# EXP03_02_2104_20212241212.net
KiCad netlist of a schematic drawn in Altium Designer
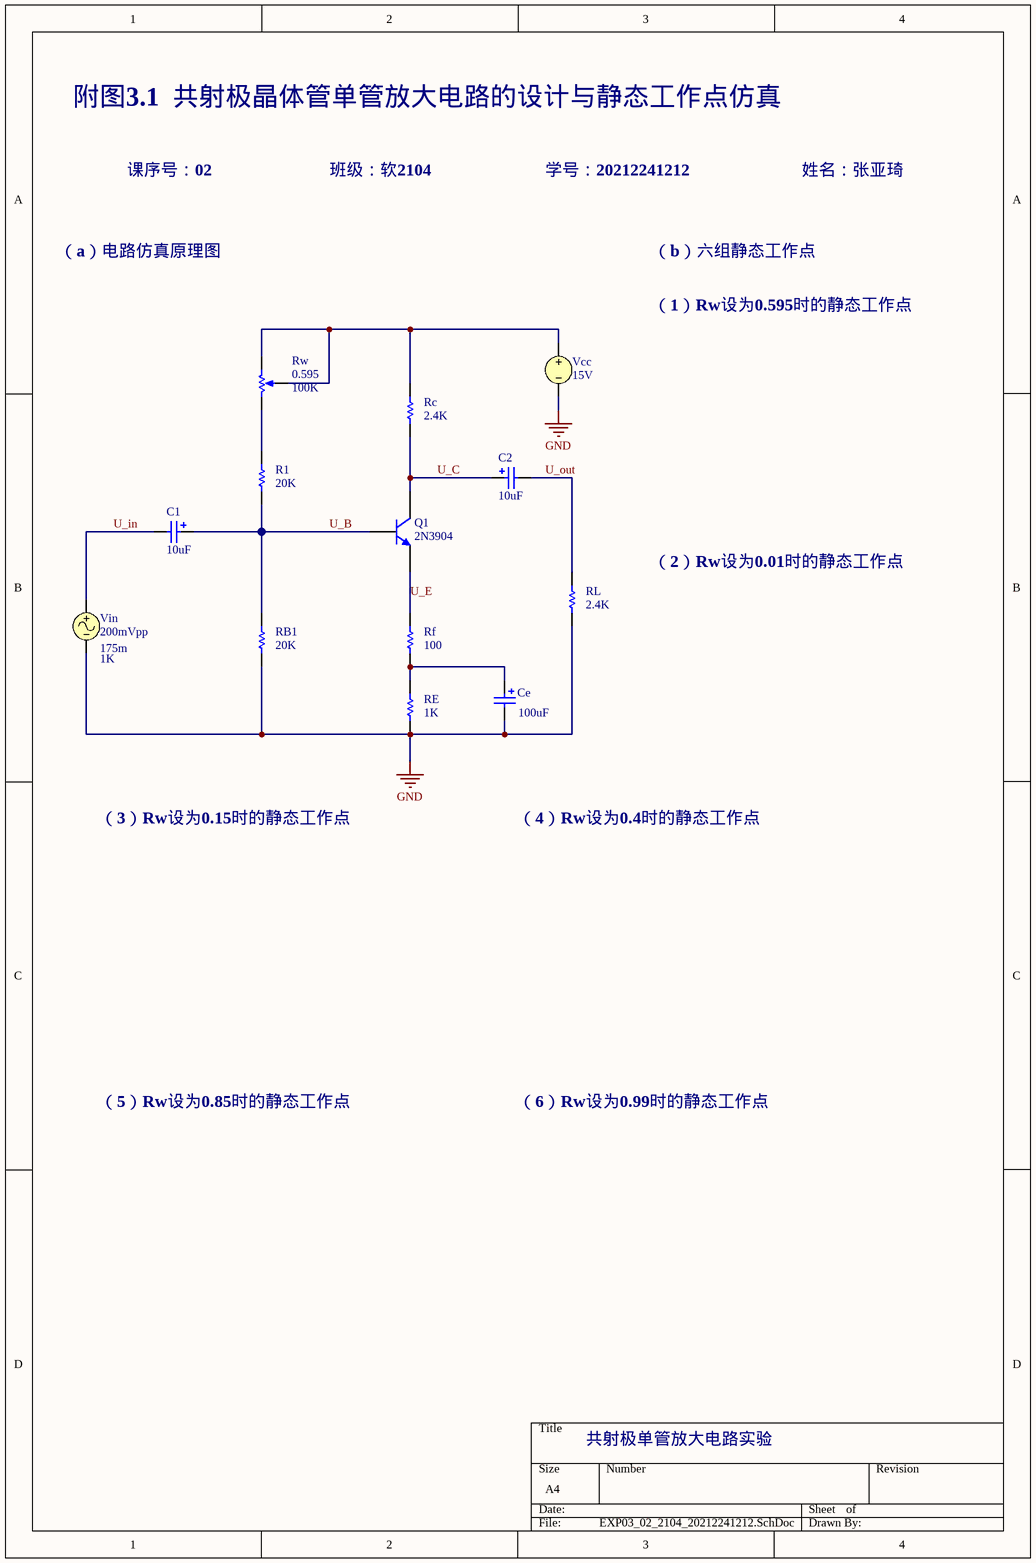
[diagram p0: EXP03_02_2104_20212241212.SchDoc]

(export (version "E")
  (design (tool "Eeschema 10.0.6"))
  (components
    (comp (ref "C1")
      (value "10uF")
      (footprint "POLAR0.8")
      (description "Polarized Capacitor (Axial)")
      (fields (field (name "PUBLISHER") "Altium Limited"))
      (libsource (lib "Miscellaneous Devices") (part "Cap Pol2"))
    )
    (comp (ref "C2")
      (value "10uF")
      (footprint "POLAR0.8")
      (description "Polarized Capacitor (Axial)")
      (fields (field (name "PUBLISHER") "Altium Limited"))
      (libsource (lib "Miscellaneous Devices") (part "Cap Pol2"))
    )
    (comp (ref "Ce")
      (value "100uF")
      (footprint "POLAR0.8")
      (description "Polarized Capacitor (Axial)")
      (fields (field (name "Comment") "Cap Pol2") (field (name "PUBLISHER") "Altium Limited"))
      (libsource (lib "") (part "Cap Pol2_1"))
    )
    (comp (ref "Q1")
      (value "2N3904")
      (footprint "TO-92A")
      (description "NPN General Purpose Amplifier")
      (fields (field (name "PUBLISHER") "Altium Limited"))
      (libsource (lib "Miscellaneous Devices") (part "2N3904"))
    )
    (comp (ref "R1")
      (value "20K")
      (footprint "AXIAL-0.3")
      (description "Resistor")
      (fields (field (name "Comment") "Res1") (field (name "PUBLISHER") "Altium Limited"))
      (libsource (lib "Miscellaneous Devices") (part "Res1"))
    )
    (comp (ref "RB1")
      (value "20K")
      (footprint "AXIAL-0.3")
      (description "Resistor")
      (fields (field (name "Comment") "Res1") (field (name "PUBLISHER") "Altium Limited"))
      (libsource (lib "Miscellaneous Devices") (part "Res1"))
    )
    (comp (ref "Rc")
      (value "2.4K")
      (footprint "AXIAL-0.3")
      (description "Resistor")
      (fields (field (name "Comment") "Res1") (field (name "PUBLISHER") "Altium Limited"))
      (libsource (lib "Miscellaneous Devices") (part "Res1"))
    )
    (comp (ref "RE")
      (value "1K")
      (footprint "AXIAL-0.3")
      (description "Resistor")
      (fields (field (name "Comment") "Res1") (field (name "PUBLISHER") "Altium Limited"))
      (libsource (lib "Miscellaneous Devices") (part "Res1"))
    )
    (comp (ref "Rf")
      (value "100")
      (footprint "AXIAL-0.3")
      (description "Resistor")
      (fields (field (name "Comment") "Res1") (field (name "PUBLISHER") "Altium Limited"))
      (libsource (lib "Miscellaneous Devices") (part "Res1"))
    )
    (comp (ref "RL")
      (value "2.4K")
      (footprint "AXIAL-0.3")
      (description "Resistor")
      (fields (field (name "Comment") "Res1") (field (name "PUBLISHER") "Altium Limited"))
      (libsource (lib "Miscellaneous Devices") (part "Res1"))
    )
    (comp (ref "Rw")
      (value "100K")
      (footprint "VR5")
      (description "Potentiometer")
      (fields
        (field (name "SET POSITION") "0.595")
        (field (name "Comment") "RPot")
        (field (name "PUBLISHER") "Altium Limited")
      )
      (libsource (lib "Miscellaneous Devices") (part "RPot"))
    )
    (comp (ref "Vcc")
      (value "15V")
      (description "Voltage Source")
      (fields (field (name "PUBLISHER") "Altium Limited"))
      (libsource (lib "Simulation Sources") (part "VSRC"))
    )
    (comp (ref "Vin")
      (value "200mVpp")
      (description "Sinusoidal Voltage Source")
      (fields
        (field (name "AMPLITUDE") "175m")
        (field (name "FREQUENCY") "1K")
        (field (name "PUBLISHER") "Altium Limited")
      )
      (libsource (lib "Simulation Sources") (part "VSIN"))
    )
  )
  (nets
    (net (code "1") (name "/U_B") (class "Default")
      (node (ref "C1") (pin "1") (pinfunction "1_1") (pintype "passive"))
      (node (ref "Q1") (pin "2") (pinfunction "B_2") (pintype "passive"))
      (node (ref "R1") (pin "1") (pinfunction "1_1") (pintype "passive"))
      (node (ref "RB1") (pin "2") (pinfunction "2_2") (pintype "passive"))
    )
    (net (code "2") (name "/U_C") (class "Default")
      (node (ref "C2") (pin "1") (pinfunction "1_1") (pintype "passive"))
      (node (ref "Q1") (pin "3") (pinfunction "C_3") (pintype "passive"))
      (node (ref "Rc") (pin "1") (pinfunction "1_1") (pintype "passive"))
    )
    (net (code "3") (name "/U_E") (class "Default")
      (node (ref "Q1") (pin "1") (pinfunction "E_1") (pintype "passive"))
      (node (ref "Rf") (pin "2") (pinfunction "2_2") (pintype "passive"))
    )
    (net (code "4") (name "/U_in") (class "Default")
      (node (ref "C1") (pin "2") (pinfunction "2_2") (pintype "passive"))
      (node (ref "Vin") (pin "1") (pinfunction "1_1") (pintype "passive"))
    )
    (net (code "5") (name "/U_out") (class "Default")
      (node (ref "C2") (pin "2") (pinfunction "2_2") (pintype "passive"))
      (node (ref "RL") (pin "2") (pinfunction "2_2") (pintype "passive"))
    )
    (net (code "6") (name "GND") (class "Default")
      (node (ref "Ce") (pin "2") (pinfunction "2_2") (pintype "passive"))
      (node (ref "RB1") (pin "1") (pinfunction "1_1") (pintype "passive"))
      (node (ref "RE") (pin "1") (pinfunction "1_1") (pintype "passive"))
      (node (ref "RL") (pin "1") (pinfunction "1_1") (pintype "passive"))
      (node (ref "Vcc") (pin "2") (pinfunction "2_2") (pintype "passive"))
      (node (ref "Vin") (pin "2") (pinfunction "2_2") (pintype "passive"))
    )
    (net (code "7") (name "Net-(Ce-Pad1)") (class "Default")
      (node (ref "Ce") (pin "1") (pinfunction "1_1") (pintype "passive"))
      (node (ref "RE") (pin "2") (pinfunction "2_2") (pintype "passive"))
      (node (ref "Rf") (pin "1") (pinfunction "1_1") (pintype "passive"))
    )
    (net (code "8") (name "Net-(Rw-BOT)") (class "Default")
      (node (ref "R1") (pin "2") (pinfunction "2_2") (pintype "passive"))
      (node (ref "Rw") (pin "2") (pinfunction "BOT_2") (pintype "passive"))
    )
    (net (code "9") (name "Net-(Rw-TAP)") (class "Default")
      (node (ref "Rc") (pin "2") (pinfunction "2_2") (pintype "passive"))
      (node (ref "Rw") (pin "1") (pinfunction "TOP_1") (pintype "passive"))
      (node (ref "Rw") (pin "3") (pinfunction "TAP_3") (pintype "passive"))
      (node (ref "Vcc") (pin "1") (pinfunction "1_1") (pintype "passive"))
    )
  )
)
